# motor-imu-cape.net
KiCad netlist of a schematic drawn in EAGLE
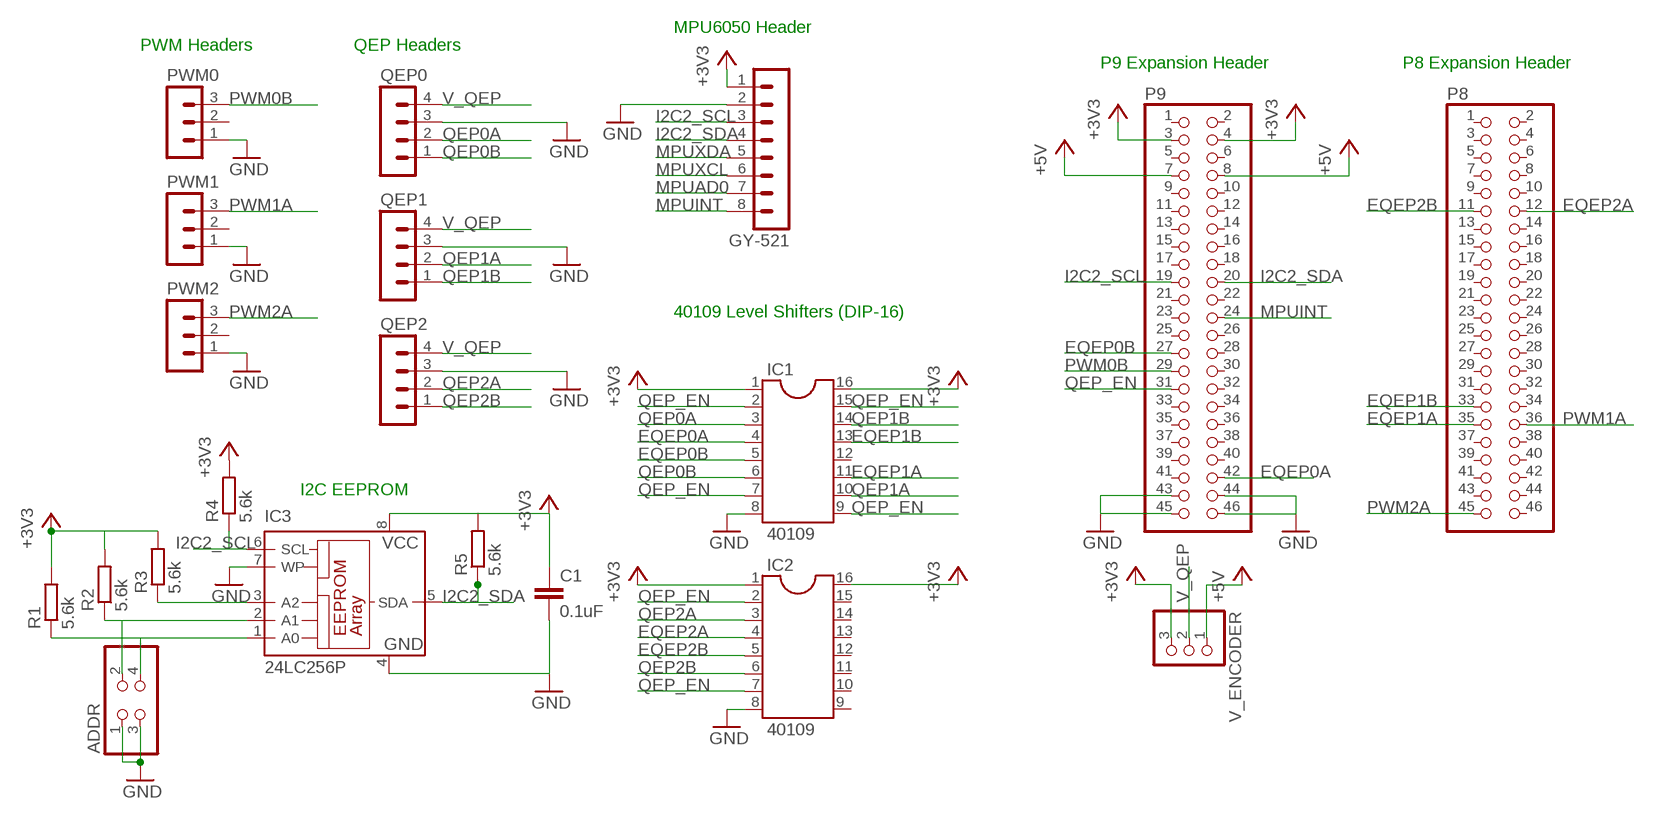
[diagram p0: schematic, sheet 1]

(export (version "E")
  (design (tool "Eeschema 10.0.6"))
  (components
    (comp (ref "ADDR")
      (value "PINHD-2X2")
      (footprint "eagle-import:2X02")
      (libsource (lib "eagle-import") (part "PINHD-2X2"))
    )
    (comp (ref "C1")
      (value "0.1uF")
      (footprint "eagle-import:C025-024X044")
      (libsource (lib "eagle-import") (part "C-EU025-024X044"))
    )
    (comp (ref "GY-521")
      (value "MA08-1")
      (footprint "eagle-import:MA08-1")
      (libsource (lib "eagle-import") (part "MA08-1"))
    )
    (comp (ref "IC1")
      (value "40109")
      (footprint "eagle-import:DIL16")
      (libsource (lib "eagle-import") (part "DIL16"))
    )
    (comp (ref "IC2")
      (value "40109")
      (footprint "eagle-import:DIL16")
      (libsource (lib "eagle-import") (part "DIL16"))
    )
    (comp (ref "IC3")
      (value "24LC256P")
      (footprint "eagle-import:DIL8")
      (fields (field (name "MF") "MICROCHIP") (field (name "MPN") "24LC256-E/P"))
      (libsource (lib "eagle-import") (part "24PLC256"))
    )
    (comp (ref "P8")
      (value "PINHD-2X23")
      (footprint "eagle-import:2X23")
      (libsource (lib "eagle-import") (part "PINHD-2X23"))
    )
    (comp (ref "P9")
      (value "PINHD-2X23")
      (footprint "eagle-import:2X23")
      (libsource (lib "eagle-import") (part "PINHD-2X23"))
    )
    (comp (ref "PWM0")
      (value "MA03-1")
      (footprint "eagle-import:MA03-1")
      (libsource (lib "eagle-import") (part "MA03-1"))
    )
    (comp (ref "PWM1")
      (value "MA03-1")
      (footprint "eagle-import:MA03-1")
      (libsource (lib "eagle-import") (part "MA03-1"))
    )
    (comp (ref "PWM2")
      (value "MA03-1")
      (footprint "eagle-import:MA03-1")
      (libsource (lib "eagle-import") (part "MA03-1"))
    )
    (comp (ref "QEP0")
      (value "MA04-1")
      (footprint "eagle-import:MA04-1")
      (libsource (lib "eagle-import") (part "MA04-1"))
    )
    (comp (ref "QEP1")
      (value "MA04-1")
      (footprint "eagle-import:MA04-1")
      (libsource (lib "eagle-import") (part "MA04-1"))
    )
    (comp (ref "QEP2")
      (value "MA04-1")
      (footprint "eagle-import:MA04-1")
      (libsource (lib "eagle-import") (part "MA04-1"))
    )
    (comp (ref "R1")
      (value "5.6k")
      (footprint "eagle-import:0204_7")
      (libsource (lib "eagle-import") (part "R-EU_0204/7"))
    )
    (comp (ref "R2")
      (value "5.6k")
      (footprint "eagle-import:0204_7")
      (libsource (lib "eagle-import") (part "R-EU_0204/7"))
    )
    (comp (ref "R3")
      (value "5.6k")
      (footprint "eagle-import:0204_7")
      (libsource (lib "eagle-import") (part "R-EU_0204/7"))
    )
    (comp (ref "R4")
      (value "5.6k")
      (footprint "eagle-import:0204_7")
      (libsource (lib "eagle-import") (part "R-EU_0204/7"))
    )
    (comp (ref "R5")
      (value "5.6k")
      (footprint "eagle-import:0204_7")
      (libsource (lib "eagle-import") (part "R-EU_0204/7"))
    )
    (comp (ref "V_ENCODER")
      (value "PINHD-1X3")
      (footprint "eagle-import:1X03")
      (libsource (lib "eagle-import") (part "PINHD-1X3"))
    )
  )
  (nets
    (net (code "1") (name "+3V3") (class "Default")
      (node (ref "C1") (pin "1") (pinfunction "1_1") (pintype "passive"))
      (node (ref "GY-521") (pin "1") (pinfunction "1_1") (pintype "passive"))
      (node (ref "IC1") (pin "1") (pinfunction "1_1") (pintype "passive"))
      (node (ref "IC1") (pin "16") (pinfunction "16_16") (pintype "passive"))
      (node (ref "IC2") (pin "1") (pinfunction "1_1") (pintype "passive"))
      (node (ref "IC2") (pin "16") (pinfunction "16_16") (pintype "passive"))
      (node (ref "IC3") (pin "8") (pinfunction "VCC_8") (pintype "power_in"))
      (node (ref "P9") (pin "3") (pinfunction "3_3") (pintype "passive"))
      (node (ref "P9") (pin "4") (pinfunction "4_4") (pintype "passive"))
      (node (ref "R1") (pin "2") (pinfunction "2_2") (pintype "passive"))
      (node (ref "R2") (pin "2") (pinfunction "2_2") (pintype "passive"))
      (node (ref "R3") (pin "2") (pinfunction "2_2") (pintype "passive"))
      (node (ref "R4") (pin "2") (pinfunction "2_2") (pintype "passive"))
      (node (ref "R5") (pin "2") (pinfunction "2_2") (pintype "passive"))
      (node (ref "V_ENCODER") (pin "3") (pinfunction "3_3") (pintype "passive"))
    )
    (net (code "2") (name "+5V") (class "Default")
      (node (ref "P9") (pin "7") (pinfunction "7_7") (pintype "passive"))
      (node (ref "P9") (pin "8") (pinfunction "8_8") (pintype "passive"))
      (node (ref "V_ENCODER") (pin "1") (pinfunction "1_1") (pintype "passive"))
    )
    (net (code "3") (name "/EQEP0A") (class "Default")
      (node (ref "IC1") (pin "4") (pinfunction "4_4") (pintype "passive"))
      (node (ref "P9") (pin "42") (pinfunction "42_42") (pintype "passive"))
    )
    (net (code "4") (name "/EQEP0B") (class "Default")
      (node (ref "IC1") (pin "5") (pinfunction "5_5") (pintype "passive"))
      (node (ref "P9") (pin "27") (pinfunction "27_27") (pintype "passive"))
    )
    (net (code "5") (name "/EQEP1A") (class "Default")
      (node (ref "IC1") (pin "11") (pinfunction "11_11") (pintype "passive"))
      (node (ref "P8") (pin "35") (pinfunction "35_35") (pintype "passive"))
    )
    (net (code "6") (name "/EQEP1B") (class "Default")
      (node (ref "IC1") (pin "13") (pinfunction "13_13") (pintype "passive"))
      (node (ref "P8") (pin "33") (pinfunction "33_33") (pintype "passive"))
    )
    (net (code "7") (name "/EQEP2A") (class "Default")
      (node (ref "IC2") (pin "4") (pinfunction "4_4") (pintype "passive"))
      (node (ref "P8") (pin "12") (pinfunction "12_12") (pintype "passive"))
    )
    (net (code "8") (name "/EQEP2B") (class "Default")
      (node (ref "IC2") (pin "5") (pinfunction "5_5") (pintype "passive"))
      (node (ref "P8") (pin "11") (pinfunction "11_11") (pintype "passive"))
    )
    (net (code "9") (name "/I2C2_SCL") (class "Default")
      (node (ref "GY-521") (pin "3") (pinfunction "3_3") (pintype "passive"))
      (node (ref "IC3") (pin "6") (pinfunction "SCL_6") (pintype "input"))
      (node (ref "P9") (pin "19") (pinfunction "19_19") (pintype "passive"))
      (node (ref "R4") (pin "1") (pinfunction "1_1") (pintype "passive"))
    )
    (net (code "10") (name "/I2C2_SDA") (class "Default")
      (node (ref "GY-521") (pin "4") (pinfunction "4_4") (pintype "passive"))
      (node (ref "IC3") (pin "5") (pinfunction "SDA_5") (pintype "bidirectional"))
      (node (ref "P9") (pin "20") (pinfunction "20_20") (pintype "passive"))
      (node (ref "R5") (pin "1") (pinfunction "1_1") (pintype "passive"))
    )
    (net (code "11") (name "/MPUAD0") (class "Default")
      (node (ref "GY-521") (pin "7") (pinfunction "7_7") (pintype "passive"))
    )
    (net (code "12") (name "/MPUINT") (class "Default")
      (node (ref "GY-521") (pin "8") (pinfunction "8_8") (pintype "passive"))
      (node (ref "P9") (pin "24") (pinfunction "24_24") (pintype "passive"))
    )
    (net (code "13") (name "/MPUXCL") (class "Default")
      (node (ref "GY-521") (pin "6") (pinfunction "6_6") (pintype "passive"))
    )
    (net (code "14") (name "/MPUXDA") (class "Default")
      (node (ref "GY-521") (pin "5") (pinfunction "5_5") (pintype "passive"))
    )
    (net (code "15") (name "/PWM0B") (class "Default")
      (node (ref "P9") (pin "29") (pinfunction "29_29") (pintype "passive"))
      (node (ref "PWM0") (pin "3") (pinfunction "3_3") (pintype "passive"))
    )
    (net (code "16") (name "/PWM1A") (class "Default")
      (node (ref "P8") (pin "36") (pinfunction "36_36") (pintype "passive"))
      (node (ref "PWM1") (pin "3") (pinfunction "3_3") (pintype "passive"))
    )
    (net (code "17") (name "/PWM2A") (class "Default")
      (node (ref "P8") (pin "45") (pinfunction "45_45") (pintype "passive"))
      (node (ref "PWM2") (pin "3") (pinfunction "3_3") (pintype "passive"))
    )
    (net (code "18") (name "/QEP0A") (class "Default")
      (node (ref "IC1") (pin "3") (pinfunction "3_3") (pintype "passive"))
      (node (ref "QEP0") (pin "2") (pinfunction "2_2") (pintype "passive"))
    )
    (net (code "19") (name "/QEP0B") (class "Default")
      (node (ref "IC1") (pin "6") (pinfunction "6_6") (pintype "passive"))
      (node (ref "QEP0") (pin "1") (pinfunction "1_1") (pintype "passive"))
    )
    (net (code "20") (name "/QEP1A") (class "Default")
      (node (ref "IC1") (pin "10") (pinfunction "10_10") (pintype "passive"))
      (node (ref "QEP1") (pin "2") (pinfunction "2_2") (pintype "passive"))
    )
    (net (code "21") (name "/QEP1B") (class "Default")
      (node (ref "IC1") (pin "14") (pinfunction "14_14") (pintype "passive"))
      (node (ref "QEP1") (pin "1") (pinfunction "1_1") (pintype "passive"))
    )
    (net (code "22") (name "/QEP2A") (class "Default")
      (node (ref "IC2") (pin "3") (pinfunction "3_3") (pintype "passive"))
      (node (ref "QEP2") (pin "2") (pinfunction "2_2") (pintype "passive"))
    )
    (net (code "23") (name "/QEP2B") (class "Default")
      (node (ref "IC2") (pin "6") (pinfunction "6_6") (pintype "passive"))
      (node (ref "QEP2") (pin "1") (pinfunction "1_1") (pintype "passive"))
    )
    (net (code "24") (name "/QEP_EN") (class "Default")
      (node (ref "IC1") (pin "15") (pinfunction "15_15") (pintype "passive"))
      (node (ref "IC1") (pin "2") (pinfunction "2_2") (pintype "passive"))
      (node (ref "IC1") (pin "7") (pinfunction "7_7") (pintype "passive"))
      (node (ref "IC1") (pin "9") (pinfunction "9_9") (pintype "passive"))
      (node (ref "IC2") (pin "2") (pinfunction "2_2") (pintype "passive"))
      (node (ref "IC2") (pin "7") (pinfunction "7_7") (pintype "passive"))
      (node (ref "P9") (pin "31") (pinfunction "31_31") (pintype "passive"))
    )
    (net (code "25") (name "/V_QEP") (class "Default")
      (node (ref "QEP0") (pin "4") (pinfunction "4_4") (pintype "passive"))
      (node (ref "QEP1") (pin "4") (pinfunction "4_4") (pintype "passive"))
      (node (ref "QEP2") (pin "4") (pinfunction "4_4") (pintype "passive"))
      (node (ref "V_ENCODER") (pin "2") (pinfunction "2_2") (pintype "passive"))
    )
    (net (code "26") (name "GND") (class "Default")
      (node (ref "ADDR") (pin "1") (pinfunction "1_1") (pintype "passive"))
      (node (ref "ADDR") (pin "3") (pinfunction "3_3") (pintype "passive"))
      (node (ref "C1") (pin "2") (pinfunction "2_2") (pintype "passive"))
      (node (ref "GY-521") (pin "2") (pinfunction "2_2") (pintype "passive"))
      (node (ref "IC1") (pin "8") (pinfunction "8_8") (pintype "passive"))
      (node (ref "IC2") (pin "8") (pinfunction "8_8") (pintype "passive"))
      (node (ref "IC3") (pin "4") (pinfunction "GND_4") (pintype "power_in"))
      (node (ref "IC3") (pin "7") (pinfunction "WP_7") (pintype "input"))
      (node (ref "P9") (pin "43") (pinfunction "43_43") (pintype "passive"))
      (node (ref "P9") (pin "44") (pinfunction "44_44") (pintype "passive"))
      (node (ref "P9") (pin "45") (pinfunction "45_45") (pintype "passive"))
      (node (ref "P9") (pin "46") (pinfunction "46_46") (pintype "passive"))
      (node (ref "PWM0") (pin "1") (pinfunction "1_1") (pintype "passive"))
      (node (ref "PWM1") (pin "1") (pinfunction "1_1") (pintype "passive"))
      (node (ref "PWM2") (pin "1") (pinfunction "1_1") (pintype "passive"))
      (node (ref "QEP0") (pin "3") (pinfunction "3_3") (pintype "passive"))
      (node (ref "QEP1") (pin "3") (pinfunction "3_3") (pintype "passive"))
      (node (ref "QEP2") (pin "3") (pinfunction "3_3") (pintype "passive"))
    )
    (net (code "27") (name "Net-(IC3-A0)") (class "Default")
      (node (ref "ADDR") (pin "4") (pinfunction "4_4") (pintype "passive"))
      (node (ref "IC3") (pin "1") (pinfunction "A0_1") (pintype "input"))
      (node (ref "R1") (pin "1") (pinfunction "1_1") (pintype "passive"))
    )
    (net (code "28") (name "Net-(IC3-A1)") (class "Default")
      (node (ref "ADDR") (pin "2") (pinfunction "2_2") (pintype "passive"))
      (node (ref "IC3") (pin "2") (pinfunction "A1_2") (pintype "input"))
      (node (ref "R2") (pin "1") (pinfunction "1_1") (pintype "passive"))
    )
    (net (code "29") (name "Net-(IC3-A2)") (class "Default")
      (node (ref "IC3") (pin "3") (pinfunction "A2_3") (pintype "input"))
      (node (ref "R3") (pin "1") (pinfunction "1_1") (pintype "passive"))
    )
    (net (code "30") (name "unconnected-(IC1-Pad12)") (class "Default")
      (node (ref "IC1") (pin "12") (pinfunction "12_12") (pintype "passive"))
    )
    (net (code "31") (name "unconnected-(IC2-Pad9)") (class "Default")
      (node (ref "IC2") (pin "9") (pinfunction "9_9") (pintype "passive"))
    )
    (net (code "32") (name "unconnected-(IC2-Pad10)") (class "Default")
      (node (ref "IC2") (pin "10") (pinfunction "10_10") (pintype "passive"))
    )
    (net (code "33") (name "unconnected-(IC2-Pad11)") (class "Default")
      (node (ref "IC2") (pin "11") (pinfunction "11_11") (pintype "passive"))
    )
    (net (code "34") (name "unconnected-(IC2-Pad12)") (class "Default")
      (node (ref "IC2") (pin "12") (pinfunction "12_12") (pintype "passive"))
    )
    (net (code "35") (name "unconnected-(IC2-Pad13)") (class "Default")
      (node (ref "IC2") (pin "13") (pinfunction "13_13") (pintype "passive"))
    )
    (net (code "36") (name "unconnected-(IC2-Pad14)") (class "Default")
      (node (ref "IC2") (pin "14") (pinfunction "14_14") (pintype "passive"))
    )
    (net (code "37") (name "unconnected-(IC2-Pad15)") (class "Default")
      (node (ref "IC2") (pin "15") (pinfunction "15_15") (pintype "passive"))
    )
    (net (code "38") (name "unconnected-(P8-Pad1)") (class "Default")
      (node (ref "P8") (pin "1") (pinfunction "1_1") (pintype "passive"))
    )
    (net (code "39") (name "unconnected-(P8-Pad2)") (class "Default")
      (node (ref "P8") (pin "2") (pinfunction "2_2") (pintype "passive"))
    )
    (net (code "40") (name "unconnected-(P8-Pad3)") (class "Default")
      (node (ref "P8") (pin "3") (pinfunction "3_3") (pintype "passive"))
    )
    (net (code "41") (name "unconnected-(P8-Pad4)") (class "Default")
      (node (ref "P8") (pin "4") (pinfunction "4_4") (pintype "passive"))
    )
    (net (code "42") (name "unconnected-(P8-Pad5)") (class "Default")
      (node (ref "P8") (pin "5") (pinfunction "5_5") (pintype "passive"))
    )
    (net (code "43") (name "unconnected-(P8-Pad6)") (class "Default")
      (node (ref "P8") (pin "6") (pinfunction "6_6") (pintype "passive"))
    )
    (net (code "44") (name "unconnected-(P8-Pad7)") (class "Default")
      (node (ref "P8") (pin "7") (pinfunction "7_7") (pintype "passive"))
    )
    (net (code "45") (name "unconnected-(P8-Pad8)") (class "Default")
      (node (ref "P8") (pin "8") (pinfunction "8_8") (pintype "passive"))
    )
    (net (code "46") (name "unconnected-(P8-Pad9)") (class "Default")
      (node (ref "P8") (pin "9") (pinfunction "9_9") (pintype "passive"))
    )
    (net (code "47") (name "unconnected-(P8-Pad10)") (class "Default")
      (node (ref "P8") (pin "10") (pinfunction "10_10") (pintype "passive"))
    )
    (net (code "48") (name "unconnected-(P8-Pad13)") (class "Default")
      (node (ref "P8") (pin "13") (pinfunction "13_13") (pintype "passive"))
    )
    (net (code "49") (name "unconnected-(P8-Pad14)") (class "Default")
      (node (ref "P8") (pin "14") (pinfunction "14_14") (pintype "passive"))
    )
    (net (code "50") (name "unconnected-(P8-Pad15)") (class "Default")
      (node (ref "P8") (pin "15") (pinfunction "15_15") (pintype "passive"))
    )
    (net (code "51") (name "unconnected-(P8-Pad16)") (class "Default")
      (node (ref "P8") (pin "16") (pinfunction "16_16") (pintype "passive"))
    )
    (net (code "52") (name "unconnected-(P8-Pad17)") (class "Default")
      (node (ref "P8") (pin "17") (pinfunction "17_17") (pintype "passive"))
    )
    (net (code "53") (name "unconnected-(P8-Pad18)") (class "Default")
      (node (ref "P8") (pin "18") (pinfunction "18_18") (pintype "passive"))
    )
    (net (code "54") (name "unconnected-(P8-Pad19)") (class "Default")
      (node (ref "P8") (pin "19") (pinfunction "19_19") (pintype "passive"))
    )
    (net (code "55") (name "unconnected-(P8-Pad20)") (class "Default")
      (node (ref "P8") (pin "20") (pinfunction "20_20") (pintype "passive"))
    )
    (net (code "56") (name "unconnected-(P8-Pad21)") (class "Default")
      (node (ref "P8") (pin "21") (pinfunction "21_21") (pintype "passive"))
    )
    (net (code "57") (name "unconnected-(P8-Pad22)") (class "Default")
      (node (ref "P8") (pin "22") (pinfunction "22_22") (pintype "passive"))
    )
    (net (code "58") (name "unconnected-(P8-Pad23)") (class "Default")
      (node (ref "P8") (pin "23") (pinfunction "23_23") (pintype "passive"))
    )
    (net (code "59") (name "unconnected-(P8-Pad24)") (class "Default")
      (node (ref "P8") (pin "24") (pinfunction "24_24") (pintype "passive"))
    )
    (net (code "60") (name "unconnected-(P8-Pad25)") (class "Default")
      (node (ref "P8") (pin "25") (pinfunction "25_25") (pintype "passive"))
    )
    (net (code "61") (name "unconnected-(P8-Pad26)") (class "Default")
      (node (ref "P8") (pin "26") (pinfunction "26_26") (pintype "passive"))
    )
    (net (code "62") (name "unconnected-(P8-Pad27)") (class "Default")
      (node (ref "P8") (pin "27") (pinfunction "27_27") (pintype "passive"))
    )
    (net (code "63") (name "unconnected-(P8-Pad28)") (class "Default")
      (node (ref "P8") (pin "28") (pinfunction "28_28") (pintype "passive"))
    )
    (net (code "64") (name "unconnected-(P8-Pad29)") (class "Default")
      (node (ref "P8") (pin "29") (pinfunction "29_29") (pintype "passive"))
    )
    (net (code "65") (name "unconnected-(P8-Pad30)") (class "Default")
      (node (ref "P8") (pin "30") (pinfunction "30_30") (pintype "passive"))
    )
    (net (code "66") (name "unconnected-(P8-Pad31)") (class "Default")
      (node (ref "P8") (pin "31") (pinfunction "31_31") (pintype "passive"))
    )
    (net (code "67") (name "unconnected-(P8-Pad32)") (class "Default")
      (node (ref "P8") (pin "32") (pinfunction "32_32") (pintype "passive"))
    )
    (net (code "68") (name "unconnected-(P8-Pad34)") (class "Default")
      (node (ref "P8") (pin "34") (pinfunction "34_34") (pintype "passive"))
    )
    (net (code "69") (name "unconnected-(P8-Pad37)") (class "Default")
      (node (ref "P8") (pin "37") (pinfunction "37_37") (pintype "passive"))
    )
    (net (code "70") (name "unconnected-(P8-Pad38)") (class "Default")
      (node (ref "P8") (pin "38") (pinfunction "38_38") (pintype "passive"))
    )
    (net (code "71") (name "unconnected-(P8-Pad39)") (class "Default")
      (node (ref "P8") (pin "39") (pinfunction "39_39") (pintype "passive"))
    )
    (net (code "72") (name "unconnected-(P8-Pad40)") (class "Default")
      (node (ref "P8") (pin "40") (pinfunction "40_40") (pintype "passive"))
    )
    (net (code "73") (name "unconnected-(P8-Pad41)") (class "Default")
      (node (ref "P8") (pin "41") (pinfunction "41_41") (pintype "passive"))
    )
    (net (code "74") (name "unconnected-(P8-Pad42)") (class "Default")
      (node (ref "P8") (pin "42") (pinfunction "42_42") (pintype "passive"))
    )
    (net (code "75") (name "unconnected-(P8-Pad43)") (class "Default")
      (node (ref "P8") (pin "43") (pinfunction "43_43") (pintype "passive"))
    )
    (net (code "76") (name "unconnected-(P8-Pad44)") (class "Default")
      (node (ref "P8") (pin "44") (pinfunction "44_44") (pintype "passive"))
    )
    (net (code "77") (name "unconnected-(P8-Pad46)") (class "Default")
      (node (ref "P8") (pin "46") (pinfunction "46_46") (pintype "passive"))
    )
    (net (code "78") (name "unconnected-(P9-Pad1)") (class "Default")
      (node (ref "P9") (pin "1") (pinfunction "1_1") (pintype "passive"))
    )
    (net (code "79") (name "unconnected-(P9-Pad2)") (class "Default")
      (node (ref "P9") (pin "2") (pinfunction "2_2") (pintype "passive"))
    )
    (net (code "80") (name "unconnected-(P9-Pad5)") (class "Default")
      (node (ref "P9") (pin "5") (pinfunction "5_5") (pintype "passive"))
    )
    (net (code "81") (name "unconnected-(P9-Pad6)") (class "Default")
      (node (ref "P9") (pin "6") (pinfunction "6_6") (pintype "passive"))
    )
    (net (code "82") (name "unconnected-(P9-Pad9)") (class "Default")
      (node (ref "P9") (pin "9") (pinfunction "9_9") (pintype "passive"))
    )
    (net (code "83") (name "unconnected-(P9-Pad10)") (class "Default")
      (node (ref "P9") (pin "10") (pinfunction "10_10") (pintype "passive"))
    )
    (net (code "84") (name "unconnected-(P9-Pad11)") (class "Default")
      (node (ref "P9") (pin "11") (pinfunction "11_11") (pintype "passive"))
    )
    (net (code "85") (name "unconnected-(P9-Pad12)") (class "Default")
      (node (ref "P9") (pin "12") (pinfunction "12_12") (pintype "passive"))
    )
    (net (code "86") (name "unconnected-(P9-Pad13)") (class "Default")
      (node (ref "P9") (pin "13") (pinfunction "13_13") (pintype "passive"))
    )
    (net (code "87") (name "unconnected-(P9-Pad14)") (class "Default")
      (node (ref "P9") (pin "14") (pinfunction "14_14") (pintype "passive"))
    )
    (net (code "88") (name "unconnected-(P9-Pad15)") (class "Default")
      (node (ref "P9") (pin "15") (pinfunction "15_15") (pintype "passive"))
    )
    (net (code "89") (name "unconnected-(P9-Pad16)") (class "Default")
      (node (ref "P9") (pin "16") (pinfunction "16_16") (pintype "passive"))
    )
    (net (code "90") (name "unconnected-(P9-Pad17)") (class "Default")
      (node (ref "P9") (pin "17") (pinfunction "17_17") (pintype "passive"))
    )
    (net (code "91") (name "unconnected-(P9-Pad18)") (class "Default")
      (node (ref "P9") (pin "18") (pinfunction "18_18") (pintype "passive"))
    )
    (net (code "92") (name "unconnected-(P9-Pad21)") (class "Default")
      (node (ref "P9") (pin "21") (pinfunction "21_21") (pintype "passive"))
    )
    (net (code "93") (name "unconnected-(P9-Pad22)") (class "Default")
      (node (ref "P9") (pin "22") (pinfunction "22_22") (pintype "passive"))
    )
    (net (code "94") (name "unconnected-(P9-Pad23)") (class "Default")
      (node (ref "P9") (pin "23") (pinfunction "23_23") (pintype "passive"))
    )
    (net (code "95") (name "unconnected-(P9-Pad25)") (class "Default")
      (node (ref "P9") (pin "25") (pinfunction "25_25") (pintype "passive"))
    )
    (net (code "96") (name "unconnected-(P9-Pad26)") (class "Default")
      (node (ref "P9") (pin "26") (pinfunction "26_26") (pintype "passive"))
    )
    (net (code "97") (name "unconnected-(P9-Pad28)") (class "Default")
      (node (ref "P9") (pin "28") (pinfunction "28_28") (pintype "passive"))
    )
    (net (code "98") (name "unconnected-(P9-Pad30)") (class "Default")
      (node (ref "P9") (pin "30") (pinfunction "30_30") (pintype "passive"))
    )
    (net (code "99") (name "unconnected-(P9-Pad32)") (class "Default")
      (node (ref "P9") (pin "32") (pinfunction "32_32") (pintype "passive"))
    )
    (net (code "100") (name "unconnected-(P9-Pad33)") (class "Default")
      (node (ref "P9") (pin "33") (pinfunction "33_33") (pintype "passive"))
    )
    (net (code "101") (name "unconnected-(P9-Pad34)") (class "Default")
      (node (ref "P9") (pin "34") (pinfunction "34_34") (pintype "passive"))
    )
    (net (code "102") (name "unconnected-(P9-Pad35)") (class "Default")
      (node (ref "P9") (pin "35") (pinfunction "35_35") (pintype "passive"))
    )
    (net (code "103") (name "unconnected-(P9-Pad36)") (class "Default")
      (node (ref "P9") (pin "36") (pinfunction "36_36") (pintype "passive"))
    )
    (net (code "104") (name "unconnected-(P9-Pad37)") (class "Default")
      (node (ref "P9") (pin "37") (pinfunction "37_37") (pintype "passive"))
    )
    (net (code "105") (name "unconnected-(P9-Pad38)") (class "Default")
      (node (ref "P9") (pin "38") (pinfunction "38_38") (pintype "passive"))
    )
    (net (code "106") (name "unconnected-(P9-Pad39)") (class "Default")
      (node (ref "P9") (pin "39") (pinfunction "39_39") (pintype "passive"))
    )
    (net (code "107") (name "unconnected-(P9-Pad40)") (class "Default")
      (node (ref "P9") (pin "40") (pinfunction "40_40") (pintype "passive"))
    )
    (net (code "108") (name "unconnected-(P9-Pad41)") (class "Default")
      (node (ref "P9") (pin "41") (pinfunction "41_41") (pintype "passive"))
    )
    (net (code "109") (name "unconnected-(PWM0-Pad2)") (class "Default")
      (node (ref "PWM0") (pin "2") (pinfunction "2_2") (pintype "passive"))
    )
    (net (code "110") (name "unconnected-(PWM1-Pad2)") (class "Default")
      (node (ref "PWM1") (pin "2") (pinfunction "2_2") (pintype "passive"))
    )
    (net (code "111") (name "unconnected-(PWM2-Pad2)") (class "Default")
      (node (ref "PWM2") (pin "2") (pinfunction "2_2") (pintype "passive"))
    )
  )
)
